# MCU0_1.net
KiCad netlist of a schematic drawn in Altium Designer
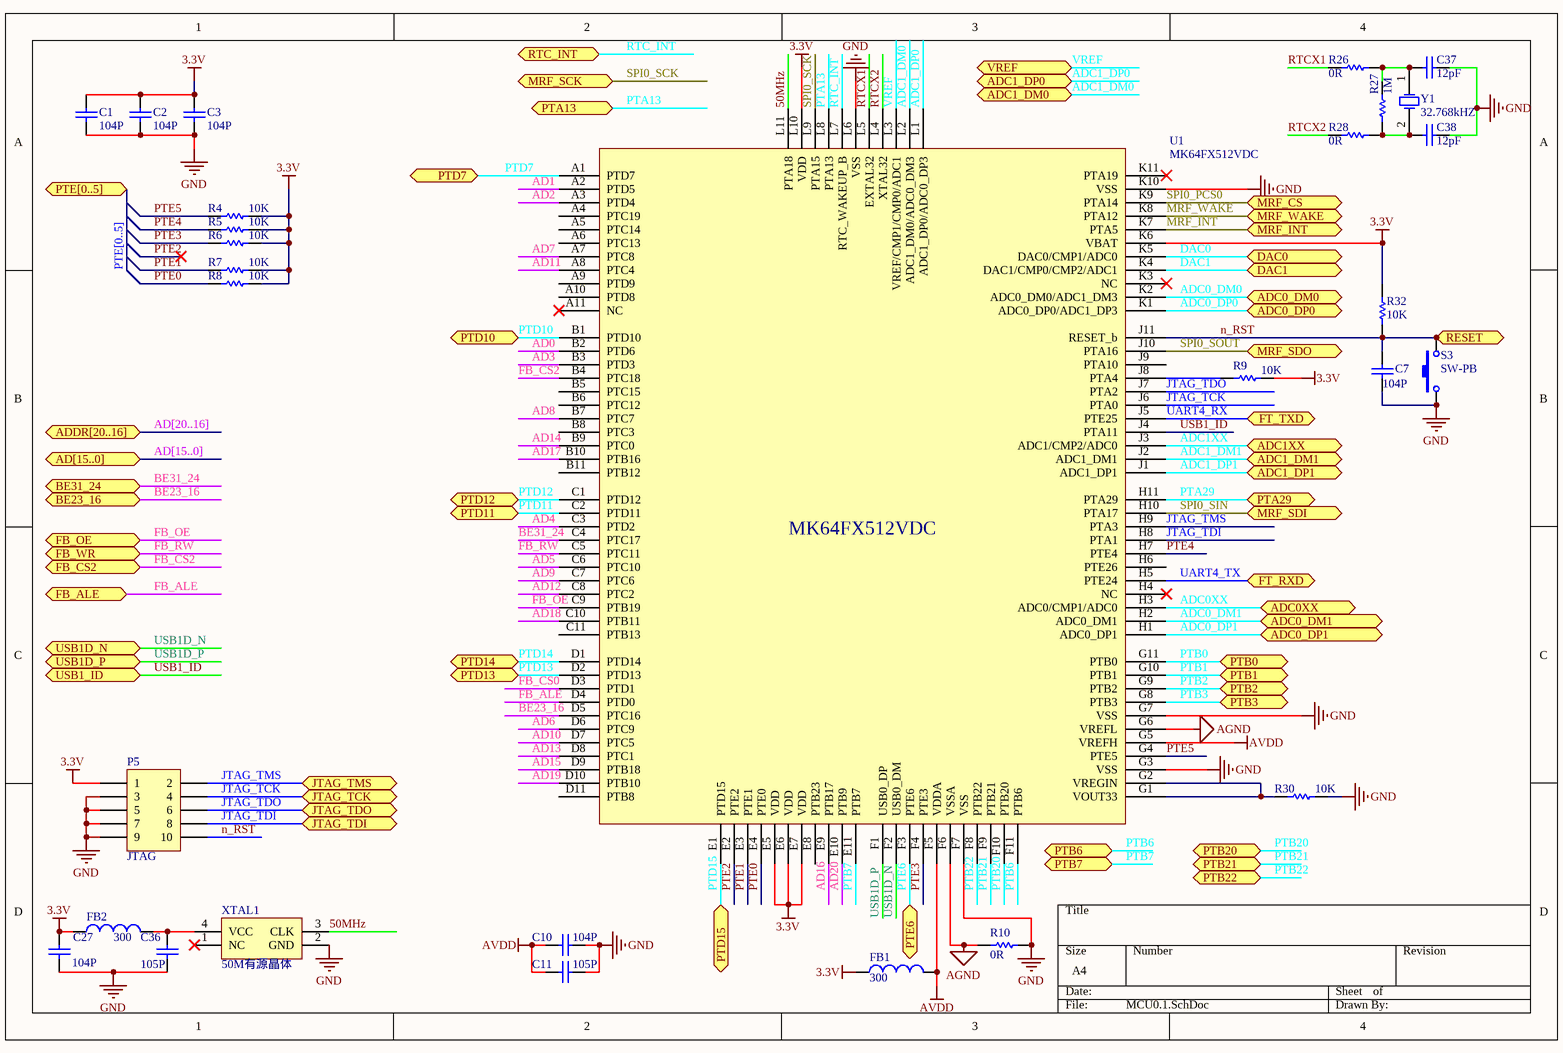
[diagram p0: MCU0.1.SchDoc]

(export (version "E")
  (design (tool "Eeschema 10.0.6"))
  (components
    (comp (ref "C1")
      (value "104P")
      (footprint "0402")
      (description "贴片电容")
      (fields (field (name "Comment") "Cap") (field (name "PUBLISHER") "Altium Limited"))
      (libsource (lib "Sparks") (part "Cap"))
    )
    (comp (ref "C2")
      (value "104P")
      (footprint "0402")
      (description "贴片电容")
      (fields (field (name "Comment") "Cap") (field (name "PUBLISHER") "Altium Limited"))
      (libsource (lib "Sparks") (part "Cap"))
    )
    (comp (ref "C3")
      (value "104P")
      (footprint "0402")
      (description "贴片电容")
      (fields (field (name "Comment") "Cap") (field (name "PUBLISHER") "Altium Limited"))
      (libsource (lib "Sparks") (part "Cap"))
    )
    (comp (ref "C7")
      (value "104P")
      (footprint "1608[0603]")
      (description "贴片电容")
      (fields (field (name "Comment") "Cap") (field (name "PUBLISHER") "Altium Limited"))
      (libsource (lib "Sparks") (part "Cap"))
    )
    (comp (ref "C10")
      (value "104P")
      (footprint "0402")
      (description "贴片电容")
      (fields (field (name "Comment") "Cap") (field (name "PUBLISHER") "Altium Limited"))
      (libsource (lib "Sparks") (part "Cap"))
    )
    (comp (ref "C11")
      (value "105P")
      (footprint "0402")
      (description "贴片电容")
      (fields (field (name "Comment") "Cap") (field (name "PUBLISHER") "Altium Limited"))
      (libsource (lib "Sparks") (part "Cap"))
    )
    (comp (ref "C27")
      (value "104P")
      (footprint "1608[0603]")
      (description "贴片电容")
      (fields (field (name "Comment") "Cap") (field (name "PUBLISHER") "Altium Limited"))
      (libsource (lib "Sparks") (part "Cap"))
    )
    (comp (ref "C36")
      (value "105P")
      (footprint "1608[0603]")
      (description "贴片电容")
      (fields (field (name "Comment") "Cap") (field (name "PUBLISHER") "Altium Limited"))
      (libsource (lib "Sparks") (part "Cap"))
    )
    (comp (ref "C37")
      (value "12pF")
      (footprint "1608[0603]")
      (description "贴片电容")
      (fields (field (name "Comment") "Cap") (field (name "PUBLISHER") "Altium Limited"))
      (libsource (lib "Sparks") (part "Cap"))
    )
    (comp (ref "C38")
      (value "12pF")
      (footprint "1608[0603]")
      (description "贴片电容")
      (fields (field (name "Comment") "Cap") (field (name "PUBLISHER") "Altium Limited"))
      (libsource (lib "Sparks") (part "Cap"))
    )
    (comp (ref "FB1")
      (value "300")
      (footprint "0402")
      (description "Inductor")
      (fields (field (name "PUBLISHER") "Altium Limited"))
      (libsource (lib "Miscellaneous Devices") (part "Inductor"))
    )
    (comp (ref "FB2")
      (value "300")
      (footprint "0402")
      (description "Inductor")
      (fields (field (name "PUBLISHER") "Altium Limited"))
      (libsource (lib "Miscellaneous Devices") (part "Inductor"))
    )
    (comp (ref "P5")
      (value "JTAG")
      (footprint "MHDR2X5")
      (description "Header, 5-Pin, Dual row")
      (fields (field (name "PUBLISHER") "Altium Limited"))
      (libsource (lib "Sparks") (part "Header 5X2"))
    )
    (comp (ref "R4")
      (value "10K")
      (footprint "1608[0603]")
      (description "贴片电阻")
      (fields (field (name "Comment") "Res") (field (name "PUBLISHER") "Altium Limited"))
      (libsource (lib "Sparks") (part "Res"))
    )
    (comp (ref "R5")
      (value "10K")
      (footprint "1608[0603]")
      (description "贴片电阻")
      (fields (field (name "Comment") "Res") (field (name "PUBLISHER") "Altium Limited"))
      (libsource (lib "Sparks") (part "Res"))
    )
    (comp (ref "R6")
      (value "10K")
      (footprint "1608[0603]")
      (description "贴片电阻")
      (fields (field (name "Comment") "Res") (field (name "PUBLISHER") "Altium Limited"))
      (libsource (lib "Sparks") (part "Res"))
    )
    (comp (ref "R7")
      (value "10K")
      (footprint "1608[0603]")
      (description "贴片电阻")
      (fields (field (name "Comment") "Res") (field (name "PUBLISHER") "Altium Limited"))
      (libsource (lib "Sparks") (part "Res"))
    )
    (comp (ref "R8")
      (value "10K")
      (footprint "1608[0603]")
      (description "贴片电阻")
      (fields (field (name "Comment") "Res") (field (name "PUBLISHER") "Altium Limited"))
      (libsource (lib "Sparks") (part "Res"))
    )
    (comp (ref "R9")
      (value "10K")
      (footprint "1608[0603]")
      (description "贴片电阻")
      (fields (field (name "Comment") "Res") (field (name "PUBLISHER") "Altium Limited"))
      (libsource (lib "Sparks") (part "Res"))
    )
    (comp (ref "R10")
      (value "0R")
      (footprint "0402")
      (description "贴片电阻")
      (fields (field (name "Comment") "Res") (field (name "PUBLISHER") "Altium Limited"))
      (libsource (lib "Sparks") (part "Res"))
    )
    (comp (ref "R26")
      (value "0R")
      (footprint "1608[0603]")
      (description "贴片电阻")
      (fields (field (name "Comment") "Res") (field (name "PUBLISHER") "Altium Limited"))
      (libsource (lib "Sparks") (part "Res"))
    )
    (comp (ref "R27")
      (value "1M")
      (footprint "1608[0603]")
      (description "贴片电阻")
      (fields (field (name "Comment") "Res") (field (name "PUBLISHER") "Altium Limited"))
      (libsource (lib "Sparks") (part "Res"))
    )
    (comp (ref "R28")
      (value "0R")
      (footprint "1608[0603]")
      (description "贴片电阻")
      (fields (field (name "Comment") "Res") (field (name "PUBLISHER") "Altium Limited"))
      (libsource (lib "Sparks") (part "Res"))
    )
    (comp (ref "R30")
      (value "10K")
      (footprint "1608[0603]")
      (description "贴片电阻")
      (fields (field (name "Comment") "Res") (field (name "PUBLISHER") "Altium Limited"))
      (libsource (lib "Sparks") (part "Res"))
    )
    (comp (ref "R32")
      (value "10K")
      (footprint "1608[0603]")
      (description "贴片电阻")
      (fields (field (name "Comment") "Res") (field (name "PUBLISHER") "Altium Limited"))
      (libsource (lib "Sparks") (part "Res"))
    )
    (comp (ref "S3")
      (value "SW-PB")
      (footprint "key 3*4*2")
      (description "Switch")
      (libsource (lib "K60-V4.0") (part "SW-PB"))
    )
    (comp (ref "U1")
      (value "MK64FX512VDC")
      (footprint "BGA121C65P11X11_800X800X50")
      (libsource (lib "2号库") (part "MK64FX512VDC"))
    )
    (comp (ref "XTAL1") (value "50M有源晶体") (footprint "XTAL7_3225") (libsource (lib "Sparks") (part "有源晶体")))
    (comp (ref "Y1")
      (value "32.768kHZ")
      (footprint "3215")
      (description "晶体振荡器")
      (fields (field (name "PUBLISHER") "Altium Limited"))
      (libsource (lib "Sparks") (part "XTAL"))
    )
  )
  (nets
    (net (code "1") (name "/50MHz") (class "Default")
      (node (ref "U1") (pin "L11") (pinfunction "PTA18_L11") (pintype "passive"))
      (node (ref "XTAL1") (pin "3") (pinfunction "CLK_3") (pintype "passive"))
    )
    (net (code "2") (name "/AD0") (class "Default")
      (node (ref "U1") (pin "B2") (pinfunction "PTD6_B2") (pintype "passive"))
    )
    (net (code "3") (name "/AD1") (class "Default")
      (node (ref "U1") (pin "A2") (pinfunction "PTD5_A2") (pintype "passive"))
    )
    (net (code "4") (name "/AD2") (class "Default")
      (node (ref "U1") (pin "A3") (pinfunction "PTD4_A3") (pintype "passive"))
    )
    (net (code "5") (name "/AD3") (class "Default")
      (node (ref "U1") (pin "B3") (pinfunction "PTD3_B3") (pintype "passive"))
    )
    (net (code "6") (name "/AD4") (class "Default")
      (node (ref "U1") (pin "C3") (pinfunction "PTD2_C3") (pintype "passive"))
    )
    (net (code "7") (name "/AD5") (class "Default")
      (node (ref "U1") (pin "C6") (pinfunction "PTC10_C6") (pintype "passive"))
    )
    (net (code "8") (name "/AD6") (class "Default")
      (node (ref "U1") (pin "D6") (pinfunction "PTC9_D6") (pintype "passive"))
    )
    (net (code "9") (name "/AD7") (class "Default")
      (node (ref "U1") (pin "A7") (pinfunction "PTC8_A7") (pintype "passive"))
    )
    (net (code "10") (name "/AD8") (class "Default")
      (node (ref "U1") (pin "B7") (pinfunction "PTC7_B7") (pintype "passive"))
    )
    (net (code "11") (name "/AD9") (class "Default")
      (node (ref "U1") (pin "C7") (pinfunction "PTC6_C7") (pintype "passive"))
    )
    (net (code "12") (name "/AD10") (class "Default")
      (node (ref "U1") (pin "D7") (pinfunction "PTC5_D7") (pintype "passive"))
    )
    (net (code "13") (name "/AD11") (class "Default")
      (node (ref "U1") (pin "A8") (pinfunction "PTC4_A8") (pintype "passive"))
    )
    (net (code "14") (name "/AD12") (class "Default")
      (node (ref "U1") (pin "C8") (pinfunction "PTC2_C8") (pintype "passive"))
    )
    (net (code "15") (name "/AD13") (class "Default")
      (node (ref "U1") (pin "D8") (pinfunction "PTC1_D8") (pintype "passive"))
    )
    (net (code "16") (name "/AD14") (class "Default")
      (node (ref "U1") (pin "B9") (pinfunction "PTC0_B9") (pintype "passive"))
    )
    (net (code "17") (name "/AD15") (class "Default")
      (node (ref "U1") (pin "D9") (pinfunction "PTB18_D9") (pintype "passive"))
    )
    (net (code "18") (name "/AD16") (class "Default")
      (node (ref "U1") (pin "E9") (pinfunction "PTB17_E9") (pintype "passive"))
    )
    (net (code "19") (name "/AD17") (class "Default")
      (node (ref "U1") (pin "B10") (pinfunction "PTB16_B10") (pintype "passive"))
    )
    (net (code "20") (name "/AD18") (class "Default")
      (node (ref "U1") (pin "C10") (pinfunction "PTB11_C10") (pintype "passive"))
    )
    (net (code "21") (name "/AD19") (class "Default")
      (node (ref "U1") (pin "D10") (pinfunction "PTB10_D10") (pintype "passive"))
    )
    (net (code "22") (name "/AD20") (class "Default")
      (node (ref "U1") (pin "E10") (pinfunction "PTB9_E10") (pintype "passive"))
    )
    (net (code "23") (name "/ADC0XX") (class "Default")
      (node (ref "U1") (pin "H3") (pinfunction "ADC0/CMP1/ADC0_H3") (pintype "passive"))
    )
    (net (code "24") (name "/ADC0_DM0") (class "Default")
      (node (ref "U1") (pin "K2") (pinfunction "ADC0_DM0/ADC1_DM3_K2") (pintype "passive"))
    )
    (net (code "25") (name "/ADC0_DM1") (class "Default")
      (node (ref "U1") (pin "H2") (pinfunction "ADC0_DM1_H2") (pintype "passive"))
    )
    (net (code "26") (name "/ADC0_DP0") (class "Default")
      (node (ref "U1") (pin "K1") (pinfunction "ADC0_DP0/ADC1_DP3_K1") (pintype "passive"))
    )
    (net (code "27") (name "/ADC0_DP1") (class "Default")
      (node (ref "U1") (pin "H1") (pinfunction "ADC0_DP1_H1") (pintype "passive"))
    )
    (net (code "28") (name "/ADC1XX") (class "Default")
      (node (ref "U1") (pin "J3") (pinfunction "ADC1/CMP2/ADC0_J3") (pintype "passive"))
    )
    (net (code "29") (name "/ADC1_DM0") (class "Default")
      (node (ref "U1") (pin "L2") (pinfunction "ADC1_DM0/ADC0_DM3_L2") (pintype "passive"))
    )
    (net (code "30") (name "/ADC1_DM1") (class "Default")
      (node (ref "U1") (pin "J2") (pinfunction "ADC1_DM1_J2") (pintype "passive"))
    )
    (net (code "31") (name "/ADC1_DP0") (class "Default")
      (node (ref "U1") (pin "L1") (pinfunction "ADC1_DP0/ADC0_DP3_L1") (pintype "passive"))
    )
    (net (code "32") (name "/ADC1_DP1") (class "Default")
      (node (ref "U1") (pin "J1") (pinfunction "ADC1_DP1_J1") (pintype "passive"))
    )
    (net (code "35") (name "/BE23_16") (class "Default")
      (node (ref "U1") (pin "D5") (pinfunction "PTC16_D5") (pintype "passive"))
    )
    (net (code "36") (name "/BE31_24") (class "Default")
      (node (ref "U1") (pin "C4") (pinfunction "PTC17_C4") (pintype "passive"))
    )
    (net (code "37") (name "/DAC0") (class "Default")
      (node (ref "U1") (pin "K5") (pinfunction "DAC0/CMP1/ADC0_K5") (pintype "passive"))
    )
    (net (code "38") (name "/DAC1") (class "Default")
      (node (ref "U1") (pin "K4") (pinfunction "DAC1/CMP0/CMP2/ADC1_K4") (pintype "passive"))
    )
    (net (code "39") (name "/FB_ALE") (class "Default")
      (node (ref "U1") (pin "D4") (pinfunction "PTD0_D4") (pintype "passive"))
    )
    (net (code "40") (name "/FB_CS0") (class "Default")
      (node (ref "U1") (pin "D3") (pinfunction "PTD1_D3") (pintype "passive"))
    )
    (net (code "41") (name "/FB_CS2") (class "Default")
      (node (ref "U1") (pin "B4") (pinfunction "PTC18_B4") (pintype "passive"))
    )
    (net (code "42") (name "/FB_OE") (class "Default")
      (node (ref "U1") (pin "C9") (pinfunction "PTB19_C9") (pintype "passive"))
    )
    (net (code "43") (name "/FB_RW") (class "Default")
      (node (ref "U1") (pin "C5") (pinfunction "PTC11_C5") (pintype "passive"))
    )
    (net (code "44") (name "/JTAG_TCK") (class "Default")
      (node (ref "P5") (pin "4") (pinfunction "4_4") (pintype "passive"))
      (node (ref "U1") (pin "J6") (pinfunction "PTA0_J6") (pintype "passive"))
    )
    (net (code "45") (name "/JTAG_TDI") (class "Default")
      (node (ref "P5") (pin "8") (pinfunction "8_8") (pintype "passive"))
      (node (ref "U1") (pin "H8") (pinfunction "PTA1_H8") (pintype "passive"))
    )
    (net (code "46") (name "/JTAG_TDO") (class "Default")
      (node (ref "P5") (pin "6") (pinfunction "6_6") (pintype "passive"))
      (node (ref "U1") (pin "J7") (pinfunction "PTA2_J7") (pintype "passive"))
    )
    (net (code "47") (name "/JTAG_TMS") (class "Default")
      (node (ref "P5") (pin "2") (pinfunction "2_2") (pintype "passive"))
      (node (ref "U1") (pin "H9") (pinfunction "PTA3_H9") (pintype "passive"))
    )
    (net (code "48") (name "/MRF_INT") (class "Default")
      (node (ref "U1") (pin "K7") (pinfunction "PTA5_K7") (pintype "passive"))
    )
    (net (code "49") (name "/MRF_WAKE") (class "Default")
      (node (ref "U1") (pin "K8") (pinfunction "PTA12_K8") (pintype "passive"))
    )
    (net (code "50") (name "/PTA13") (class "Default")
      (node (ref "U1") (pin "L8") (pinfunction "PTA13_L8") (pintype "passive"))
    )
    (net (code "51") (name "/PTA29") (class "Default")
      (node (ref "U1") (pin "H11") (pinfunction "PTA29_H11") (pintype "passive"))
    )
    (net (code "52") (name "/PTB0") (class "Default")
      (node (ref "U1") (pin "G11") (pinfunction "PTB0_G11") (pintype "passive"))
    )
    (net (code "53") (name "/PTB1") (class "Default")
      (node (ref "U1") (pin "G10") (pinfunction "PTB1_G10") (pintype "passive"))
    )
    (net (code "54") (name "/PTB2") (class "Default")
      (node (ref "U1") (pin "G9") (pinfunction "PTB2_G9") (pintype "passive"))
    )
    (net (code "55") (name "/PTB3") (class "Default")
      (node (ref "U1") (pin "G8") (pinfunction "PTB3_G8") (pintype "passive"))
    )
    (net (code "56") (name "/PTB6") (class "Default")
      (node (ref "U1") (pin "F11") (pinfunction "PTB6_F11") (pintype "passive"))
    )
    (net (code "57") (name "/PTB7") (class "Default")
      (node (ref "U1") (pin "E11") (pinfunction "PTB7_E11") (pintype "passive"))
    )
    (net (code "58") (name "/PTB20") (class "Default")
      (node (ref "U1") (pin "F10") (pinfunction "PTB20_F10") (pintype "passive"))
    )
    (net (code "59") (name "/PTB21") (class "Default")
      (node (ref "U1") (pin "F9") (pinfunction "PTB21_F9") (pintype "passive"))
    )
    (net (code "60") (name "/PTB22") (class "Default")
      (node (ref "U1") (pin "F8") (pinfunction "PTB22_F8") (pintype "passive"))
    )
    (net (code "61") (name "/PTD7") (class "Default")
      (node (ref "U1") (pin "A1") (pinfunction "PTD7_A1") (pintype "passive"))
    )
    (net (code "62") (name "/PTD10") (class "Default")
      (node (ref "U1") (pin "B1") (pinfunction "PTD10_B1") (pintype "passive"))
    )
    (net (code "63") (name "/PTD11") (class "Default")
      (node (ref "U1") (pin "C2") (pinfunction "PTD11_C2") (pintype "passive"))
    )
    (net (code "64") (name "/PTD12") (class "Default")
      (node (ref "U1") (pin "C1") (pinfunction "PTD12_C1") (pintype "passive"))
    )
    (net (code "65") (name "/PTD13") (class "Default")
      (node (ref "U1") (pin "D2") (pinfunction "PTD13_D2") (pintype "passive"))
    )
    (net (code "66") (name "/PTD14") (class "Default")
      (node (ref "U1") (pin "D1") (pinfunction "PTD14_D1") (pintype "passive"))
    )
    (net (code "67") (name "/PTD15") (class "Default")
      (node (ref "U1") (pin "E1") (pinfunction "PTD15_E1") (pintype "passive"))
    )
    (net (code "68") (name "/PTE0") (class "Default")
      (node (ref "R8") (pin "2") (pinfunction "2_2") (pintype "passive"))
      (node (ref "U1") (pin "E4") (pinfunction "PTE0_E4") (pintype "passive"))
    )
    (net (code "69") (name "/PTE1") (class "Default")
      (node (ref "R7") (pin "2") (pinfunction "2_2") (pintype "passive"))
      (node (ref "U1") (pin "E3") (pinfunction "PTE1_E3") (pintype "passive"))
    )
    (net (code "70") (name "/PTE2") (class "Default")
      (node (ref "U1") (pin "E2") (pinfunction "PTE2_E2") (pintype "passive"))
    )
    (net (code "71") (name "/PTE3") (class "Default")
      (node (ref "R6") (pin "2") (pinfunction "2_2") (pintype "passive"))
      (node (ref "U1") (pin "F4") (pinfunction "PTE3_F4") (pintype "passive"))
    )
    (net (code "72") (name "/PTE4") (class "Default")
      (node (ref "R5") (pin "2") (pinfunction "2_2") (pintype "passive"))
      (node (ref "U1") (pin "H7") (pinfunction "PTE4_H7") (pintype "passive"))
    )
    (net (code "73") (name "/PTE5") (class "Default")
      (node (ref "R4") (pin "2") (pinfunction "2_2") (pintype "passive"))
      (node (ref "U1") (pin "G4") (pinfunction "PTE5_G4") (pintype "passive"))
    )
    (net (code "74") (name "/PTE6") (class "Default")
      (node (ref "U1") (pin "F3") (pinfunction "PTE6_F3") (pintype "passive"))
    )
    (net (code "76") (name "/RTCX1") (class "Default")
      (node (ref "R26") (pin "2") (pinfunction "2_2") (pintype "passive"))
      (node (ref "U1") (pin "L5") (pinfunction "EXTAL32_L5") (pintype "passive"))
    )
    (net (code "77") (name "/RTCX2") (class "Default")
      (node (ref "R28") (pin "2") (pinfunction "2_2") (pintype "passive"))
      (node (ref "U1") (pin "L4") (pinfunction "XTAL32_L4") (pintype "passive"))
    )
    (net (code "78") (name "/RTC_INT") (class "Default")
      (node (ref "U1") (pin "L7") (pinfunction "RTC_WAKEUP_B_L7") (pintype "passive"))
    )
    (net (code "79") (name "/SPI0_PCS0") (class "Default")
      (node (ref "U1") (pin "K9") (pinfunction "PTA14_K9") (pintype "passive"))
    )
    (net (code "80") (name "/SPI0_SCK") (class "Default")
      (node (ref "U1") (pin "L9") (pinfunction "PTA15_L9") (pintype "passive"))
    )
    (net (code "81") (name "/SPI0_SIN") (class "Default")
      (node (ref "U1") (pin "H10") (pinfunction "PTA17_H10") (pintype "passive"))
    )
    (net (code "82") (name "/SPI0_SOUT") (class "Default")
      (node (ref "U1") (pin "J10") (pinfunction "PTA16_J10") (pintype "passive"))
    )
    (net (code "83") (name "/UART4_RX") (class "Default")
      (node (ref "U1") (pin "J5") (pinfunction "PTE25_J5") (pintype "passive"))
    )
    (net (code "84") (name "/UART4_TX") (class "Default")
      (node (ref "U1") (pin "H5") (pinfunction "PTE24_H5") (pintype "passive"))
    )
    (net (code "85") (name "/USB1D_N") (class "Default")
      (node (ref "U1") (pin "F2") (pinfunction "USB0_DM_F2") (pintype "passive"))
    )
    (net (code "86") (name "/USB1D_P") (class "Default")
      (node (ref "U1") (pin "F1") (pinfunction "USB0_DP_F1") (pintype "passive"))
    )
    (net (code "87") (name "/USB1_ID") (class "Default")
      (node (ref "U1") (pin "J4") (pinfunction "PTA11_J4") (pintype "passive"))
    )
    (net (code "88") (name "/VREF") (class "Default")
      (node (ref "U1") (pin "L3") (pinfunction "VREF/CMP1/CMP0/ADC1_L3") (pintype "passive"))
    )
    (net (code "89") (name "/n_RST") (class "Default")
      (node (ref "C7") (pin "2") (pinfunction "2_2") (pintype "passive"))
      (node (ref "P5") (pin "10") (pinfunction "10_10") (pintype "passive"))
      (node (ref "R32") (pin "2") (pinfunction "2_2") (pintype "passive"))
      (node (ref "S3") (pin "2") (pinfunction "2_2") (pintype "passive"))
      (node (ref "U1") (pin "J11") (pinfunction "RESET_b_J11") (pintype "passive"))
    )
    (net (code "90") (name "3.3V") (class "Default")
      (node (ref "C1") (pin "2") (pinfunction "2_2") (pintype "passive"))
      (node (ref "C2") (pin "2") (pinfunction "2_2") (pintype "passive"))
      (node (ref "C27") (pin "2") (pinfunction "2_2") (pintype "passive"))
      (node (ref "C3") (pin "2") (pinfunction "2_2") (pintype "passive"))
      (node (ref "FB1") (pin "1") (pinfunction "1_1") (pintype "passive"))
      (node (ref "FB2") (pin "1") (pinfunction "1_1") (pintype "passive"))
      (node (ref "P5") (pin "1") (pinfunction "1_1") (pintype "passive"))
      (node (ref "R32") (pin "1") (pinfunction "1_1") (pintype "passive"))
      (node (ref "R4") (pin "1") (pinfunction "1_1") (pintype "passive"))
      (node (ref "R5") (pin "1") (pinfunction "1_1") (pintype "passive"))
      (node (ref "R6") (pin "1") (pinfunction "1_1") (pintype "passive"))
      (node (ref "R7") (pin "1") (pinfunction "1_1") (pintype "passive"))
      (node (ref "R8") (pin "1") (pinfunction "1_1") (pintype "passive"))
      (node (ref "R9") (pin "1") (pinfunction "1_1") (pintype "passive"))
      (node (ref "U1") (pin "E5") (pinfunction "VDD_E5") (pintype "passive"))
      (node (ref "U1") (pin "E6") (pinfunction "VDD_E6") (pintype "passive"))
      (node (ref "U1") (pin "E7") (pinfunction "VDD_E7") (pintype "passive"))
      (node (ref "U1") (pin "K6") (pinfunction "VBAT_K6") (pintype "passive"))
      (node (ref "U1") (pin "L10") (pinfunction "VDD_L10") (pintype "passive"))
    )
    (net (code "91") (name "AGND") (class "Default")
      (node (ref "R10") (pin "2") (pinfunction "2_2") (pintype "passive"))
      (node (ref "U1") (pin "F6") (pinfunction "VSSA_F6") (pintype "passive"))
      (node (ref "U1") (pin "G6") (pinfunction "VREFL_G6") (pintype "passive"))
    )
    (net (code "92") (name "AVDD") (class "Default")
      (node (ref "C10") (pin "1") (pinfunction "1_1") (pintype "passive"))
      (node (ref "C11") (pin "1") (pinfunction "1_1") (pintype "passive"))
      (node (ref "FB1") (pin "2") (pinfunction "2_2") (pintype "passive"))
      (node (ref "U1") (pin "F5") (pinfunction "VDDA_F5") (pintype "passive"))
      (node (ref "U1") (pin "G5") (pinfunction "VREFH_G5") (pintype "passive"))
    )
    (net (code "93") (name "GND") (class "Default")
      (node (ref "C1") (pin "1") (pinfunction "1_1") (pintype "passive"))
      (node (ref "C10") (pin "2") (pinfunction "2_2") (pintype "passive"))
      (node (ref "C11") (pin "2") (pinfunction "2_2") (pintype "passive"))
      (node (ref "C2") (pin "1") (pinfunction "1_1") (pintype "passive"))
      (node (ref "C27") (pin "1") (pinfunction "1_1") (pintype "passive"))
      (node (ref "C3") (pin "1") (pinfunction "1_1") (pintype "passive"))
      (node (ref "C36") (pin "1") (pinfunction "1_1") (pintype "passive"))
      (node (ref "C37") (pin "1") (pinfunction "1_1") (pintype "passive"))
      (node (ref "C38") (pin "1") (pinfunction "1_1") (pintype "passive"))
      (node (ref "C7") (pin "1") (pinfunction "1_1") (pintype "passive"))
      (node (ref "P5") (pin "3") (pinfunction "3_3") (pintype "passive"))
      (node (ref "P5") (pin "5") (pinfunction "5_5") (pintype "passive"))
      (node (ref "P5") (pin "7") (pinfunction "7_7") (pintype "passive"))
      (node (ref "P5") (pin "9") (pinfunction "9_9") (pintype "passive"))
      (node (ref "R10") (pin "1") (pinfunction "1_1") (pintype "passive"))
      (node (ref "R30") (pin "1") (pinfunction "1_1") (pintype "passive"))
      (node (ref "S3") (pin "1") (pinfunction "1_1") (pintype "passive"))
      (node (ref "U1") (pin "F7") (pinfunction "VSS_F7") (pintype "passive"))
      (node (ref "U1") (pin "G3") (pinfunction "VSS_G3") (pintype "passive"))
      (node (ref "U1") (pin "G7") (pinfunction "VSS_G7") (pintype "passive"))
      (node (ref "U1") (pin "K10") (pinfunction "VSS_K10") (pintype "passive"))
      (node (ref "U1") (pin "L6") (pinfunction "VSS_L6") (pintype "passive"))
      (node (ref "XTAL1") (pin "2") (pinfunction "GND_2") (pintype "passive"))
    )
    (net (code "94") (name "Net-(U1-PTA4)") (class "Default")
      (node (ref "R9") (pin "2") (pinfunction "2_2") (pintype "passive"))
      (node (ref "U1") (pin "J8") (pinfunction "PTA4_J8") (pintype "passive"))
    )
    (net (code "95") (name "Net-(U1-VOUT33)") (class "Default")
      (node (ref "R30") (pin "2") (pinfunction "2_2") (pintype "passive"))
      (node (ref "U1") (pin "G1") (pinfunction "VOUT33_G1") (pintype "passive"))
      (node (ref "U1") (pin "G2") (pinfunction "VREGIN_G2") (pintype "passive"))
    )
    (net (code "96") (name "Net-(XTAL1-VCC)") (class "Default")
      (node (ref "C36") (pin "2") (pinfunction "2_2") (pintype "passive"))
      (node (ref "FB2") (pin "2") (pinfunction "2_2") (pintype "passive"))
      (node (ref "XTAL1") (pin "4") (pinfunction "VCC_4") (pintype "passive"))
    )
    (net (code "97") (name "Net-(Y1-OSC1)") (class "Default")
      (node (ref "C37") (pin "2") (pinfunction "2_2") (pintype "passive"))
      (node (ref "R26") (pin "1") (pinfunction "1_1") (pintype "passive"))
      (node (ref "R27") (pin "1") (pinfunction "1_1") (pintype "passive"))
      (node (ref "Y1") (pin "1") (pinfunction "OSC1_1") (pintype "passive"))
    )
    (net (code "98") (name "Net-(Y1-OSC2)") (class "Default")
      (node (ref "C38") (pin "2") (pinfunction "2_2") (pintype "passive"))
      (node (ref "R27") (pin "2") (pinfunction "2_2") (pintype "passive"))
      (node (ref "R28") (pin "1") (pinfunction "1_1") (pintype "passive"))
      (node (ref "Y1") (pin "2") (pinfunction "OSC2_2") (pintype "passive"))
    )
    (net (code "99") (name "unconnected-(U1-NC-PadA11)") (class "Default")
      (node (ref "U1") (pin "A11") (pinfunction "NC_A11") (pintype "passive+no_connect"))
    )
    (net (code "100") (name "unconnected-(U1-NC-PadH4)") (class "Default")
      (node (ref "U1") (pin "H4") (pinfunction "NC_H4") (pintype "passive+no_connect"))
    )
    (net (code "101") (name "unconnected-(U1-NC-PadK3)") (class "Default")
      (node (ref "U1") (pin "K3") (pinfunction "NC_K3") (pintype "passive+no_connect"))
    )
    (net (code "102") (name "unconnected-(U1-PTA10-PadJ9)") (class "Default")
      (node (ref "U1") (pin "J9") (pinfunction "PTA10_J9") (pintype "passive"))
    )
    (net (code "103") (name "unconnected-(U1-PTA19-PadK11)") (class "Default")
      (node (ref "U1") (pin "K11") (pinfunction "PTA19_K11") (pintype "passive+no_connect"))
    )
    (net (code "104") (name "unconnected-(U1-PTB8-PadD11)") (class "Default")
      (node (ref "U1") (pin "D11") (pinfunction "PTB8_D11") (pintype "passive"))
    )
    (net (code "105") (name "unconnected-(U1-PTB12-PadB11)") (class "Default")
      (node (ref "U1") (pin "B11") (pinfunction "PTB12_B11") (pintype "passive"))
    )
    (net (code "106") (name "unconnected-(U1-PTB13-PadC11)") (class "Default")
      (node (ref "U1") (pin "C11") (pinfunction "PTB13_C11") (pintype "passive"))
    )
    (net (code "107") (name "unconnected-(U1-PTB23-PadE8)") (class "Default")
      (node (ref "U1") (pin "E8") (pinfunction "PTB23_E8") (pintype "passive"))
    )
    (net (code "108") (name "unconnected-(U1-PTC3-PadB8)") (class "Default")
      (node (ref "U1") (pin "B8") (pinfunction "PTC3_B8") (pintype "passive"))
    )
    (net (code "109") (name "unconnected-(U1-PTC12-PadB6)") (class "Default")
      (node (ref "U1") (pin "B6") (pinfunction "PTC12_B6") (pintype "passive"))
    )
    (net (code "110") (name "unconnected-(U1-PTC13-PadA6)") (class "Default")
      (node (ref "U1") (pin "A6") (pinfunction "PTC13_A6") (pintype "passive"))
    )
    (net (code "111") (name "unconnected-(U1-PTC14-PadA5)") (class "Default")
      (node (ref "U1") (pin "A5") (pinfunction "PTC14_A5") (pintype "passive"))
    )
    (net (code "112") (name "unconnected-(U1-PTC15-PadB5)") (class "Default")
      (node (ref "U1") (pin "B5") (pinfunction "PTC15_B5") (pintype "passive"))
    )
    (net (code "113") (name "unconnected-(U1-PTC19-PadA4)") (class "Default")
      (node (ref "U1") (pin "A4") (pinfunction "PTC19_A4") (pintype "passive"))
    )
    (net (code "114") (name "unconnected-(U1-PTD8-PadA10)") (class "Default")
      (node (ref "U1") (pin "A10") (pinfunction "PTD8_A10") (pintype "passive"))
    )
    (net (code "115") (name "unconnected-(U1-PTD9-PadA9)") (class "Default")
      (node (ref "U1") (pin "A9") (pinfunction "PTD9_A9") (pintype "passive"))
    )
    (net (code "116") (name "unconnected-(U1-PTE26-PadH6)") (class "Default")
      (node (ref "U1") (pin "H6") (pinfunction "PTE26_H6") (pintype "passive"))
    )
    (net (code "117") (name "unconnected-(XTAL1-NC-Pad1)") (class "Default")
      (node (ref "XTAL1") (pin "1") (pinfunction "NC_1") (pintype "passive+no_connect"))
    )
  )
)
